# L1_1.net
KiCad netlist of a schematic drawn in EAGLE
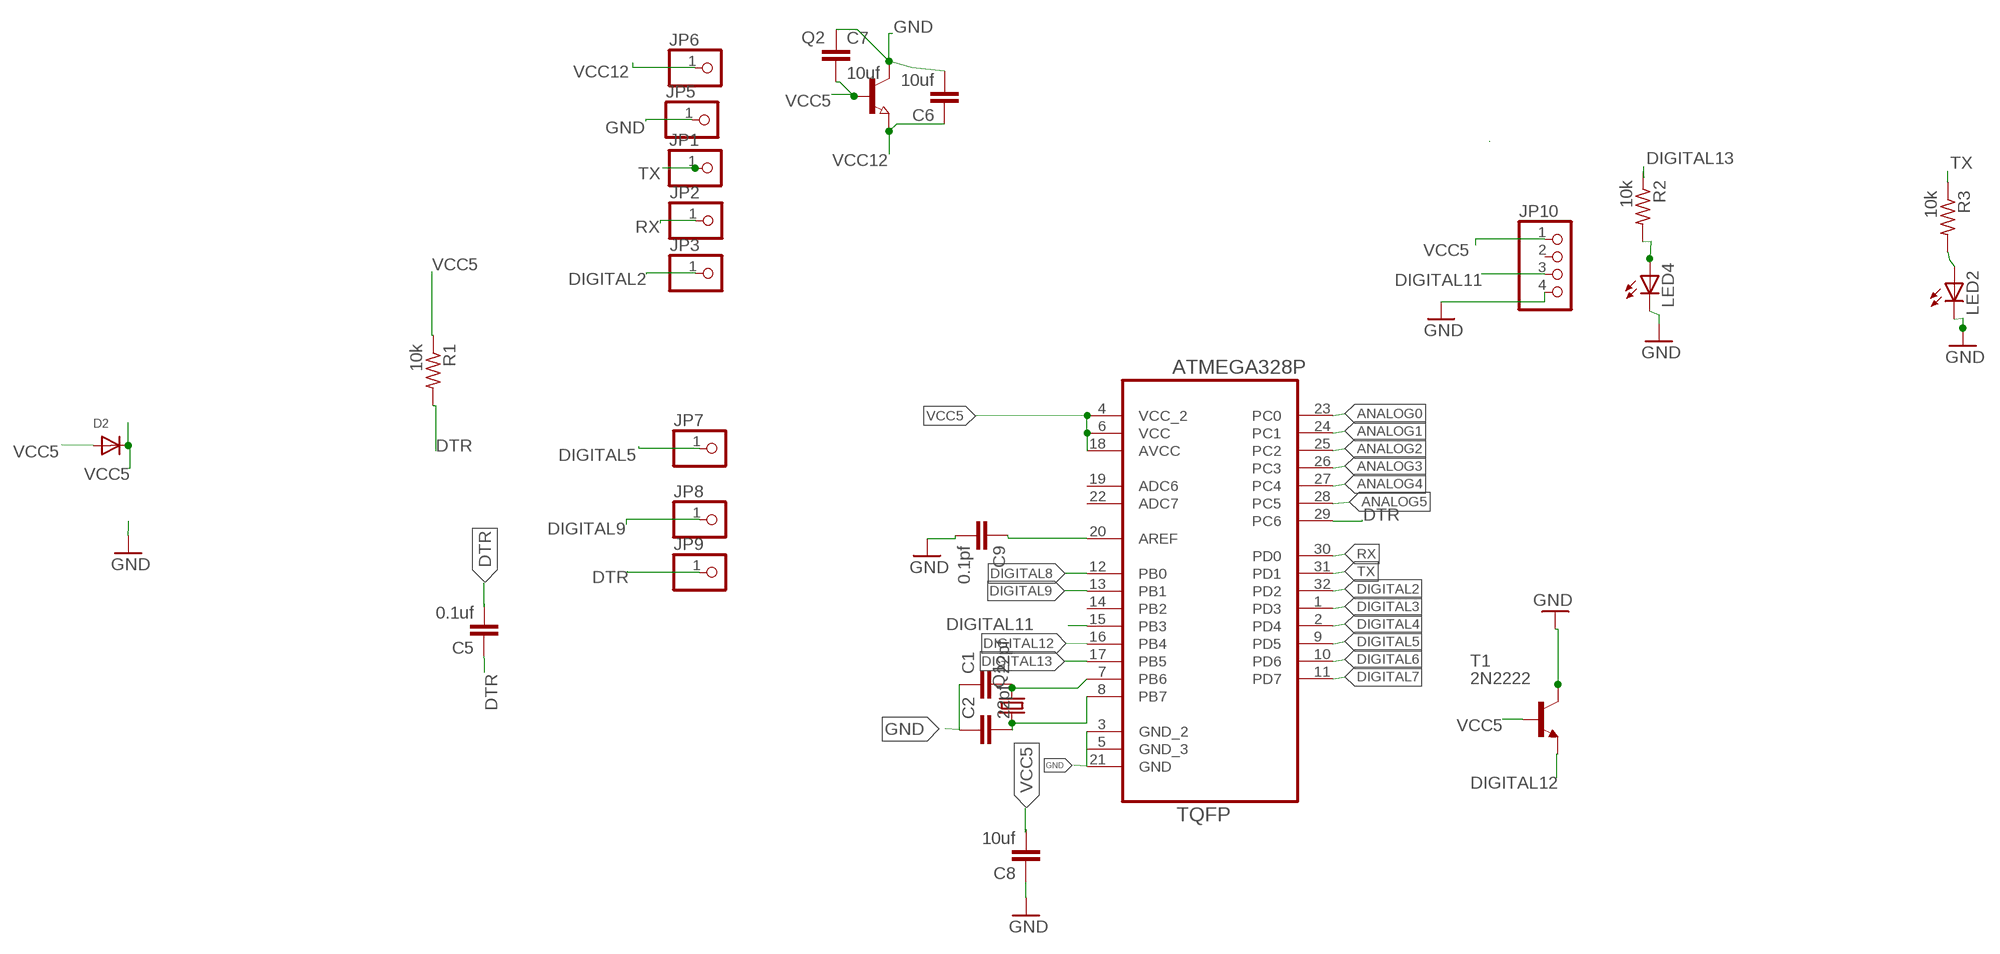
[diagram p0: schematic, sheet 1]

(export (version "E")
  (design (tool "Eeschema 10.0.6"))
  (components
    (comp (ref "C1")
      (value "22pf")
      (footprint "eagle-import:C0603")
      (libsource (lib "eagle-import") (part "C-EUC0603"))
    )
    (comp (ref "C2")
      (value "22pf")
      (footprint "eagle-import:C0603")
      (libsource (lib "eagle-import") (part "C-EUC0603"))
    )
    (comp (ref "C5")
      (value "0.1uf")
      (footprint "eagle-import:C0805")
      (libsource (lib "eagle-import") (part "C-EUC0805"))
    )
    (comp (ref "C6")
      (value "10uf")
      (footprint "eagle-import:C0805")
      (libsource (lib "eagle-import") (part "C-EUC0805"))
    )
    (comp (ref "C7")
      (value "10uf")
      (footprint "eagle-import:C0805")
      (libsource (lib "eagle-import") (part "C-EUC0805"))
    )
    (comp (ref "C8")
      (value "10uf")
      (footprint "eagle-import:C0805")
      (libsource (lib "eagle-import") (part "C-EUC0805"))
    )
    (comp (ref "C9")
      (value "0.1pf")
      (footprint "eagle-import:C0805")
      (libsource (lib "eagle-import") (part "C-EUC0805"))
    )
    (comp (ref "D2")
      (value "DIODESMA")
      (footprint "eagle-import:SMADIODE")
      (libsource (lib "eagle-import") (part "DIODESMA"))
    )
    (comp (ref "JP1")
      (value "PINHD-1X1")
      (footprint "eagle-import:1X01")
      (libsource (lib "eagle-import") (part "PINHD-1X1"))
    )
    (comp (ref "JP2")
      (value "PINHD-1X1")
      (footprint "eagle-import:1X01")
      (libsource (lib "eagle-import") (part "PINHD-1X1"))
    )
    (comp (ref "JP3")
      (value "PINHD-1X1")
      (footprint "eagle-import:1X01")
      (libsource (lib "eagle-import") (part "PINHD-1X1"))
    )
    (comp (ref "JP5")
      (value "PINHD-1X1")
      (footprint "eagle-import:1X01")
      (libsource (lib "eagle-import") (part "PINHD-1X1"))
    )
    (comp (ref "JP6")
      (value "PINHD-1X1")
      (footprint "eagle-import:1X01")
      (libsource (lib "eagle-import") (part "PINHD-1X1"))
    )
    (comp (ref "JP7")
      (value "PINHD-1X1")
      (footprint "eagle-import:1X01")
      (libsource (lib "eagle-import") (part "PINHD-1X1"))
    )
    (comp (ref "JP8")
      (value "PINHD-1X1")
      (footprint "eagle-import:1X01")
      (libsource (lib "eagle-import") (part "PINHD-1X1"))
    )
    (comp (ref "JP9")
      (value "PINHD-1X1")
      (footprint "eagle-import:1X01")
      (libsource (lib "eagle-import") (part "PINHD-1X1"))
    )
    (comp (ref "JP10")
      (value "PINHD-1X4")
      (footprint "eagle-import:1X04")
      (libsource (lib "eagle-import") (part "PINHD-1X4"))
    )
    (comp (ref "LED2")
      (value "LEDCHIPLED_0805")
      (footprint "eagle-import:CHIPLED_0805")
      (libsource (lib "eagle-import") (part "LEDCHIPLED_0805"))
    )
    (comp (ref "LED4")
      (value "LEDCHIPLED_0805")
      (footprint "eagle-import:CHIPLED_0805")
      (libsource (lib "eagle-import") (part "LEDCHIPLED_0805"))
    )
    (comp (ref "Q1")
      (value "CRYSTALTC26V")
      (footprint "eagle-import:TC26V")
      (libsource (lib "eagle-import") (part "CRYSTALTC26V"))
    )
    (comp (ref "Q2")
      (value "NPN-TRANSISTOR_SOT23")
      (footprint "eagle-import:SOT23")
      (libsource (lib "eagle-import") (part "NPN-TRANSISTOR_SOT23"))
    )
    (comp (ref "R1")
      (value "10k")
      (footprint "eagle-import:R0603")
      (libsource (lib "eagle-import") (part "R-US_R0603"))
    )
    (comp (ref "R2")
      (value "10k")
      (footprint "eagle-import:R0603")
      (libsource (lib "eagle-import") (part "R-US_R0603"))
    )
    (comp (ref "R3")
      (value "10k")
      (footprint "eagle-import:R0603")
      (libsource (lib "eagle-import") (part "R-US_R0603"))
    )
    (comp (ref "T1")
      (value "2N2222")
      (footprint "eagle-import:TO92-EBC-OVAL")
      (libsource (lib "eagle-import") (part "2N2222"))
    )
    (comp (ref "U2")
      (value "ATMEGA328P-AU")
      (footprint "eagle-import:QFP80P900X900X120-32N")
      (libsource (lib "eagle-import") (part "ATMEGA328P-AU"))
    )
  )
  (nets
    (net (code "1") (name "/DIGITAL11") (class "Default")
      (node (ref "JP10") (pin "3") (pinfunction "3_3") (pintype "passive"))
      (node (ref "U2") (pin "15") (pinfunction "PB3_15") (pintype "bidirectional"))
    )
    (net (code "2") (name "/VCC12") (class "Default")
      (node (ref "C6") (pin "1") (pinfunction "1_1") (pintype "passive"))
      (node (ref "JP6") (pin "1") (pinfunction "1_1") (pintype "passive"))
      (node (ref "Q2") (pin "2") (pinfunction "E_2") (pintype "passive"))
    )
    (net (code "3") (name "ANALOG0") (class "Default")
      (node (ref "U2") (pin "23") (pinfunction "PC0_23") (pintype "bidirectional"))
    )
    (net (code "4") (name "ANALOG1") (class "Default")
      (node (ref "U2") (pin "24") (pinfunction "PC1_24") (pintype "bidirectional"))
    )
    (net (code "5") (name "ANALOG2") (class "Default")
      (node (ref "U2") (pin "25") (pinfunction "PC2_25") (pintype "bidirectional"))
    )
    (net (code "6") (name "ANALOG3") (class "Default")
      (node (ref "U2") (pin "26") (pinfunction "PC3_26") (pintype "bidirectional"))
    )
    (net (code "7") (name "ANALOG4") (class "Default")
      (node (ref "U2") (pin "27") (pinfunction "PC4_27") (pintype "bidirectional"))
    )
    (net (code "8") (name "ANALOG5") (class "Default")
      (node (ref "U2") (pin "28") (pinfunction "PC5_28") (pintype "bidirectional"))
    )
    (net (code "9") (name "DIGITAL2") (class "Default")
      (node (ref "JP3") (pin "1") (pinfunction "1_1") (pintype "passive"))
      (node (ref "U2") (pin "32") (pinfunction "PD2_32") (pintype "bidirectional"))
    )
    (net (code "10") (name "DIGITAL3") (class "Default")
      (node (ref "U2") (pin "1") (pinfunction "PD3_1") (pintype "bidirectional"))
    )
    (net (code "11") (name "DIGITAL4") (class "Default")
      (node (ref "U2") (pin "2") (pinfunction "PD4_2") (pintype "bidirectional"))
    )
    (net (code "12") (name "DIGITAL5") (class "Default")
      (node (ref "JP7") (pin "1") (pinfunction "1_1") (pintype "passive"))
      (node (ref "U2") (pin "9") (pinfunction "PD5_9") (pintype "bidirectional"))
    )
    (net (code "13") (name "DIGITAL6") (class "Default")
      (node (ref "U2") (pin "10") (pinfunction "PD6_10") (pintype "bidirectional"))
    )
    (net (code "14") (name "DIGITAL7") (class "Default")
      (node (ref "U2") (pin "11") (pinfunction "PD7_11") (pintype "bidirectional"))
    )
    (net (code "15") (name "DIGITAL8") (class "Default")
      (node (ref "U2") (pin "12") (pinfunction "PB0_12") (pintype "bidirectional"))
    )
    (net (code "16") (name "DIGITAL9") (class "Default")
      (node (ref "JP8") (pin "1") (pinfunction "1_1") (pintype "passive"))
      (node (ref "U2") (pin "13") (pinfunction "PB1_13") (pintype "bidirectional"))
    )
    (net (code "17") (name "DIGITAL12") (class "Default")
      (node (ref "T1") (pin "E") (pinfunction "E_E") (pintype "passive"))
      (node (ref "U2") (pin "16") (pinfunction "PB4_16") (pintype "bidirectional"))
    )
    (net (code "18") (name "DIGITAL13") (class "Default")
      (node (ref "R2") (pin "1") (pinfunction "1_1") (pintype "passive"))
      (node (ref "U2") (pin "17") (pinfunction "PB5_17") (pintype "bidirectional"))
    )
    (net (code "19") (name "DTR") (class "Default")
      (node (ref "C5") (pin "1") (pinfunction "1_1") (pintype "passive"))
      (node (ref "C5") (pin "2") (pinfunction "2_2") (pintype "passive"))
      (node (ref "JP9") (pin "1") (pinfunction "1_1") (pintype "passive"))
      (node (ref "R1") (pin "2") (pinfunction "2_2") (pintype "passive"))
      (node (ref "U2") (pin "29") (pinfunction "PC6_29") (pintype "bidirectional"))
    )
    (net (code "20") (name "GND") (class "Default")
      (node (ref "C1") (pin "1") (pinfunction "1_1") (pintype "passive"))
      (node (ref "C2") (pin "1") (pinfunction "1_1") (pintype "passive"))
      (node (ref "C6") (pin "2") (pinfunction "2_2") (pintype "passive"))
      (node (ref "C7") (pin "1") (pinfunction "1_1") (pintype "passive"))
      (node (ref "C8") (pin "1") (pinfunction "1_1") (pintype "passive"))
      (node (ref "C9") (pin "2") (pinfunction "2_2") (pintype "passive"))
      (node (ref "JP10") (pin "4") (pinfunction "4_4") (pintype "passive"))
      (node (ref "JP5") (pin "1") (pinfunction "1_1") (pintype "passive"))
      (node (ref "LED2") (pin "C") (pinfunction "C_C") (pintype "passive"))
      (node (ref "LED4") (pin "C") (pinfunction "C_C") (pintype "passive"))
      (node (ref "Q2") (pin "3") (pinfunction "C_3") (pintype "passive"))
      (node (ref "T1") (pin "C") (pinfunction "C_C") (pintype "passive"))
      (node (ref "U2") (pin "21") (pinfunction "GND_21") (pintype "passive"))
      (node (ref "U2") (pin "3") (pinfunction "GND_2_3") (pintype "passive"))
      (node (ref "U2") (pin "5") (pinfunction "GND_3_5") (pintype "passive"))
    )
    (net (code "21") (name "Net-(LED2-PadA)") (class "Default")
      (node (ref "LED2") (pin "A") (pinfunction "A_A") (pintype "passive"))
      (node (ref "R3") (pin "2") (pinfunction "2_2") (pintype "passive"))
    )
    (net (code "22") (name "Net-(LED4-PadA)") (class "Default")
      (node (ref "LED4") (pin "A") (pinfunction "A_A") (pintype "passive"))
      (node (ref "R2") (pin "2") (pinfunction "2_2") (pintype "passive"))
    )
    (net (code "23") (name "Net-(U2-AREF)") (class "Default")
      (node (ref "C9") (pin "1") (pinfunction "1_1") (pintype "passive"))
      (node (ref "U2") (pin "20") (pinfunction "AREF_20") (pintype "input"))
    )
    (net (code "24") (name "Net-(U2-PB6)") (class "Default")
      (node (ref "C1") (pin "2") (pinfunction "2_2") (pintype "passive"))
      (node (ref "Q1") (pin "2") (pinfunction "2_2") (pintype "passive"))
      (node (ref "U2") (pin "7") (pinfunction "PB6_7") (pintype "bidirectional"))
    )
    (net (code "25") (name "Net-(U2-PB7)") (class "Default")
      (node (ref "C2") (pin "2") (pinfunction "2_2") (pintype "passive"))
      (node (ref "Q1") (pin "1") (pinfunction "1_1") (pintype "passive"))
      (node (ref "U2") (pin "8") (pinfunction "PB7_8") (pintype "bidirectional"))
    )
    (net (code "26") (name "RX") (class "Default")
      (node (ref "JP2") (pin "1") (pinfunction "1_1") (pintype "passive"))
      (node (ref "U2") (pin "30") (pinfunction "PD0_30") (pintype "bidirectional"))
    )
    (net (code "27") (name "TX") (class "Default")
      (node (ref "JP1") (pin "1") (pinfunction "1_1") (pintype "passive"))
      (node (ref "R3") (pin "1") (pinfunction "1_1") (pintype "passive"))
      (node (ref "U2") (pin "31") (pinfunction "PD1_31") (pintype "bidirectional"))
    )
    (net (code "28") (name "VCC5") (class "Default")
      (node (ref "C7") (pin "2") (pinfunction "2_2") (pintype "passive"))
      (node (ref "C8") (pin "2") (pinfunction "2_2") (pintype "passive"))
      (node (ref "D2") (pin "A") (pinfunction "A_A") (pintype "passive"))
      (node (ref "D2") (pin "C") (pinfunction "C_C") (pintype "passive"))
      (node (ref "JP10") (pin "1") (pinfunction "1_1") (pintype "passive"))
      (node (ref "Q2") (pin "1") (pinfunction "B_1") (pintype "passive"))
      (node (ref "R1") (pin "1") (pinfunction "1_1") (pintype "passive"))
      (node (ref "T1") (pin "B") (pinfunction "B_B") (pintype "passive"))
      (node (ref "U2") (pin "18") (pinfunction "AVCC_18") (pintype "power_in"))
      (node (ref "U2") (pin "4") (pinfunction "VCC_2_4") (pintype "power_in"))
      (node (ref "U2") (pin "6") (pinfunction "VCC_6") (pintype "power_in"))
    )
    (net (code "29") (name "unconnected-(JP10-Pad2)") (class "Default")
      (node (ref "JP10") (pin "2") (pinfunction "2_2") (pintype "passive"))
    )
    (net (code "30") (name "unconnected-(U2-ADC6-Pad19)") (class "Default")
      (node (ref "U2") (pin "19") (pinfunction "ADC6_19") (pintype "input"))
    )
    (net (code "31") (name "unconnected-(U2-ADC7-Pad22)") (class "Default")
      (node (ref "U2") (pin "22") (pinfunction "ADC7_22") (pintype "input"))
    )
    (net (code "32") (name "unconnected-(U2-PB2-Pad14)") (class "Default")
      (node (ref "U2") (pin "14") (pinfunction "PB2_14") (pintype "bidirectional"))
    )
  )
)
